# Schatten3.net
KiCad netlist of a schematic drawn in EAGLE
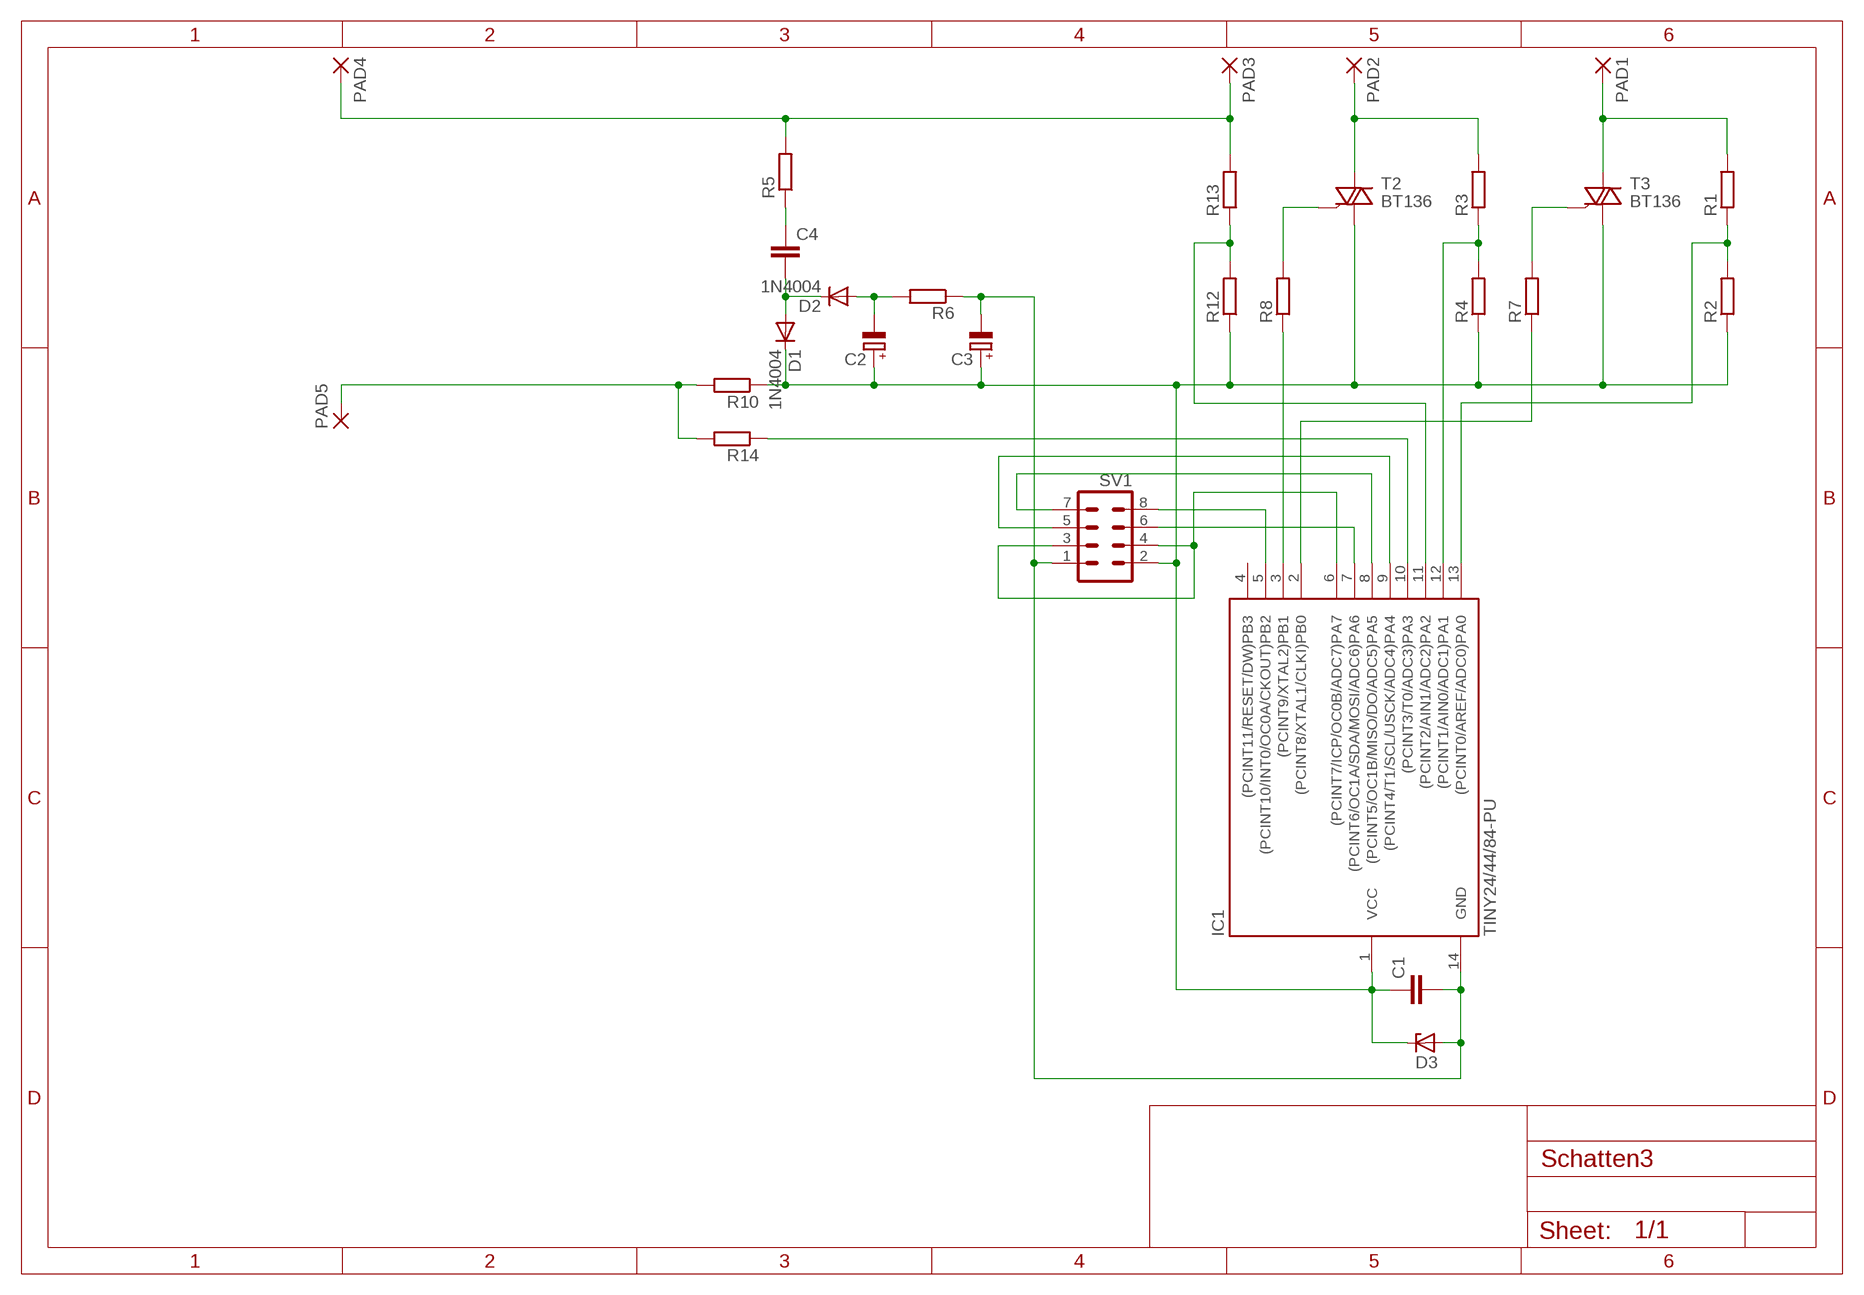
[diagram p0: schematic, sheet 1]

(export (version "E")
  (design (tool "Eeschema 10.0.6"))
  (components
    (comp (ref "C1")
      (value "C-EUC3225")
      (footprint "eagle-import:C3225")
      (libsource (lib "eagle-import") (part "C-EUC3225"))
    )
    (comp (ref "C2")
      (value "CPOL-EUE5-8.5")
      (footprint "eagle-import:E5-8,5")
      (libsource (lib "eagle-import") (part "CPOL-EUE5-8.5"))
    )
    (comp (ref "C3")
      (value "CPOL-EUE5-8.5")
      (footprint "eagle-import:E5-8,5")
      (libsource (lib "eagle-import") (part "CPOL-EUE5-8.5"))
    )
    (comp (ref "C4")
      (value "C-EU150-064X183")
      (footprint "eagle-import:C150-064X183")
      (libsource (lib "eagle-import") (part "C-EU150-064X183"))
    )
    (comp (ref "D1")
      (value "1N4004")
      (footprint "eagle-import:DO41-10")
      (libsource (lib "eagle-import") (part "1N4004"))
    )
    (comp (ref "D2")
      (value "1N4004")
      (footprint "eagle-import:DO41-10")
      (libsource (lib "eagle-import") (part "1N4004"))
    )
    (comp (ref "D3")
      (value "ZENER-DIODEZD-7.5")
      (footprint "eagle-import:ZDIO-7.5")
      (libsource (lib "eagle-import") (part "ZENER-DIODEZD-7.5"))
    )
    (comp (ref "IC1")
      (value "TINY24/44/84-PU")
      (footprint "eagle-import:DIL14")
      (libsource (lib "eagle-import") (part "TINY24/44/84-PU"))
    )
    (comp (ref "PAD1")
      (value "1,6/0,9")
      (footprint "eagle-import:1,6_0,9")
      (libsource (lib "eagle-import") (part "1,6/0,9"))
    )
    (comp (ref "PAD2")
      (value "1,6/0,9")
      (footprint "eagle-import:1,6_0,9")
      (libsource (lib "eagle-import") (part "1,6/0,9"))
    )
    (comp (ref "PAD3")
      (value "1,6/0,9")
      (footprint "eagle-import:1,6_0,9")
      (libsource (lib "eagle-import") (part "1,6/0,9"))
    )
    (comp (ref "PAD4")
      (value "1,6/0,9")
      (footprint "eagle-import:1,6_0,9")
      (libsource (lib "eagle-import") (part "1,6/0,9"))
    )
    (comp (ref "PAD5")
      (value "1,6/0,9")
      (footprint "eagle-import:1,6_0,9")
      (libsource (lib "eagle-import") (part "1,6/0,9"))
    )
    (comp (ref "R1")
      (value "R-EU_0207/10")
      (footprint "eagle-import:0207_10")
      (libsource (lib "eagle-import") (part "R-EU_0207/10"))
    )
    (comp (ref "R2")
      (value "R-EU_0207/10")
      (footprint "eagle-import:0207_10")
      (libsource (lib "eagle-import") (part "R-EU_0207/10"))
    )
    (comp (ref "R3")
      (value "R-EU_0207/10")
      (footprint "eagle-import:0207_10")
      (libsource (lib "eagle-import") (part "R-EU_0207/10"))
    )
    (comp (ref "R4")
      (value "R-EU_0207/10")
      (footprint "eagle-import:0207_10")
      (libsource (lib "eagle-import") (part "R-EU_0207/10"))
    )
    (comp (ref "R5")
      (value "R-EU_0207/10")
      (footprint "eagle-import:0207_10")
      (libsource (lib "eagle-import") (part "R-EU_0207/10"))
    )
    (comp (ref "R6")
      (value "R-EU_0207/10")
      (footprint "eagle-import:0207_10")
      (libsource (lib "eagle-import") (part "R-EU_0207/10"))
    )
    (comp (ref "R7")
      (value "R-EU_0207/10")
      (footprint "eagle-import:0207_10")
      (libsource (lib "eagle-import") (part "R-EU_0207/10"))
    )
    (comp (ref "R8")
      (value "R-EU_0207/10")
      (footprint "eagle-import:0207_10")
      (libsource (lib "eagle-import") (part "R-EU_0207/10"))
    )
    (comp (ref "R10")
      (value "R-EU_0207/10")
      (footprint "eagle-import:0207_10")
      (libsource (lib "eagle-import") (part "R-EU_0207/10"))
    )
    (comp (ref "R12")
      (value "R-EU_0207/10")
      (footprint "eagle-import:0207_10")
      (libsource (lib "eagle-import") (part "R-EU_0207/10"))
    )
    (comp (ref "R13")
      (value "R-EU_0207/10")
      (footprint "eagle-import:0207_10")
      (libsource (lib "eagle-import") (part "R-EU_0207/10"))
    )
    (comp (ref "R14")
      (value "R-EU_0207/10")
      (footprint "eagle-import:0207_10")
      (libsource (lib "eagle-import") (part "R-EU_0207/10"))
    )
    (comp (ref "SV1")
      (value "MA04-2")
      (footprint "eagle-import:MA04-2")
      (libsource (lib "eagle-import") (part "MA04-2"))
    )
    (comp (ref "T2")
      (value "BT136")
      (footprint "eagle-import:TO220AB")
      (libsource (lib "eagle-import") (part "BT136"))
    )
    (comp (ref "T3")
      (value "BT136")
      (footprint "eagle-import:TO220AB")
      (libsource (lib "eagle-import") (part "BT136"))
    )
  )
  (nets
    (net (code "1") (name "Net-(C2-Pad-)") (class "Default")
      (node (ref "C2") (pin "-") (pinfunction "-_-") (pintype "passive"))
      (node (ref "D2") (pin "A") (pinfunction "A_A") (pintype "passive"))
      (node (ref "R6") (pin "2") (pinfunction "2_2") (pintype "passive"))
    )
    (net (code "2") (name "Net-(C4-Pad1)") (class "Default")
      (node (ref "C4") (pin "1") (pinfunction "1_1") (pintype "passive"))
      (node (ref "R5") (pin "1") (pinfunction "1_1") (pintype "passive"))
    )
    (net (code "3") (name "Net-(C4-Pad2)") (class "Default")
      (node (ref "C4") (pin "2") (pinfunction "2_2") (pintype "passive"))
      (node (ref "D1") (pin "A") (pinfunction "A_A") (pintype "passive"))
      (node (ref "D2") (pin "C") (pinfunction "C_C") (pintype "passive"))
    )
    (net (code "4") (name "Net-(IC1-(PCINT0{slash}AREF{slash}ADC0)PA0)") (class "Default")
      (node (ref "IC1") (pin "13") (pinfunction "(PCINT0/AREF/ADC0)PA0_13") (pintype "bidirectional"))
      (node (ref "R1") (pin "1") (pinfunction "1_1") (pintype "passive"))
      (node (ref "R2") (pin "2") (pinfunction "2_2") (pintype "passive"))
    )
    (net (code "5") (name "Net-(IC1-(PCINT1{slash}AIN0{slash}ADC1)PA1)") (class "Default")
      (node (ref "IC1") (pin "12") (pinfunction "(PCINT1/AIN0/ADC1)PA1_12") (pintype "bidirectional"))
      (node (ref "R3") (pin "1") (pinfunction "1_1") (pintype "passive"))
      (node (ref "R4") (pin "2") (pinfunction "2_2") (pintype "passive"))
    )
    (net (code "6") (name "Net-(IC1-(PCINT2{slash}AIN1{slash}ADC2)PA2)") (class "Default")
      (node (ref "IC1") (pin "11") (pinfunction "(PCINT2/AIN1/ADC2)PA2_11") (pintype "bidirectional"))
      (node (ref "R12") (pin "2") (pinfunction "2_2") (pintype "passive"))
      (node (ref "R13") (pin "1") (pinfunction "1_1") (pintype "passive"))
    )
    (net (code "7") (name "Net-(IC1-(PCINT3{slash}T0{slash}ADC3)PA3)") (class "Default")
      (node (ref "IC1") (pin "10") (pinfunction "(PCINT3/T0/ADC3)PA3_10") (pintype "bidirectional"))
      (node (ref "R14") (pin "1") (pinfunction "1_1") (pintype "passive"))
    )
    (net (code "8") (name "Net-(IC1-(PCINT4{slash}T1{slash}SCL{slash}USCK{slash}ADC4)PA4)") (class "Default")
      (node (ref "IC1") (pin "9") (pinfunction "(PCINT4/T1/SCL/USCK/ADC4)PA4_9") (pintype "bidirectional"))
      (node (ref "SV1") (pin "5") (pinfunction "5_5") (pintype "passive"))
    )
    (net (code "9") (name "Net-(IC1-(PCINT5{slash}OC1B{slash}MISO{slash}DO{slash}ADC5)PA5)") (class "Default")
      (node (ref "IC1") (pin "8") (pinfunction "(PCINT5/OC1B/MISO/DO/ADC5)PA5_8") (pintype "bidirectional"))
      (node (ref "SV1") (pin "7") (pinfunction "7_7") (pintype "passive"))
    )
    (net (code "10") (name "Net-(IC1-(PCINT6{slash}OC1A{slash}SDA{slash}MOSI{slash}ADC6)PA6)") (class "Default")
      (node (ref "IC1") (pin "7") (pinfunction "(PCINT6/OC1A/SDA/MOSI/ADC6)PA6_7") (pintype "bidirectional"))
      (node (ref "SV1") (pin "6") (pinfunction "6_6") (pintype "passive"))
    )
    (net (code "11") (name "Net-(IC1-(PCINT7{slash}ICP{slash}OC0B{slash}ADC7)PA7)") (class "Default")
      (node (ref "IC1") (pin "6") (pinfunction "(PCINT7/ICP/OC0B/ADC7)PA7_6") (pintype "bidirectional"))
      (node (ref "SV1") (pin "3") (pinfunction "3_3") (pintype "passive"))
      (node (ref "SV1") (pin "4") (pinfunction "4_4") (pintype "passive"))
    )
    (net (code "12") (name "Net-(IC1-(PCINT8{slash}XTAL1{slash}CLKI)PB0)") (class "Default")
      (node (ref "IC1") (pin "2") (pinfunction "(PCINT8/XTAL1/CLKI)PB0_2") (pintype "bidirectional"))
      (node (ref "R7") (pin "1") (pinfunction "1_1") (pintype "passive"))
    )
    (net (code "13") (name "Net-(IC1-(PCINT9{slash}XTAL2)PB1)") (class "Default")
      (node (ref "IC1") (pin "3") (pinfunction "(PCINT9/XTAL2)PB1_3") (pintype "bidirectional"))
      (node (ref "R8") (pin "1") (pinfunction "1_1") (pintype "passive"))
    )
    (net (code "14") (name "Net-(IC1-(PCINT10{slash}INT0{slash}OC0A{slash}CKOUT)PB2)") (class "Default")
      (node (ref "IC1") (pin "5") (pinfunction "(PCINT10/INT0/OC0A/CKOUT)PB2_5") (pintype "bidirectional"))
      (node (ref "SV1") (pin "8") (pinfunction "8_8") (pintype "passive"))
    )
    (net (code "15") (name "Net-(IC1-GND)") (class "Default")
      (node (ref "C1") (pin "2") (pinfunction "2_2") (pintype "passive"))
      (node (ref "C3") (pin "-") (pinfunction "-_-") (pintype "passive"))
      (node (ref "D3") (pin "A") (pinfunction "A_A") (pintype "passive"))
      (node (ref "IC1") (pin "14") (pinfunction "GND_14") (pintype "power_in"))
      (node (ref "R6") (pin "1") (pinfunction "1_1") (pintype "passive"))
      (node (ref "SV1") (pin "1") (pinfunction "1_1") (pintype "passive"))
    )
    (net (code "16") (name "Net-(IC1-VCC)") (class "Default")
      (node (ref "C1") (pin "1") (pinfunction "1_1") (pintype "passive"))
      (node (ref "C2") (pin "+") (pinfunction "+_+") (pintype "passive"))
      (node (ref "C3") (pin "+") (pinfunction "+_+") (pintype "passive"))
      (node (ref "D1") (pin "C") (pinfunction "C_C") (pintype "passive"))
      (node (ref "D3") (pin "C") (pinfunction "C_C") (pintype "passive"))
      (node (ref "IC1") (pin "1") (pinfunction "VCC_1") (pintype "power_in"))
      (node (ref "R10") (pin "1") (pinfunction "1_1") (pintype "passive"))
      (node (ref "R12") (pin "1") (pinfunction "1_1") (pintype "passive"))
      (node (ref "R2") (pin "1") (pinfunction "1_1") (pintype "passive"))
      (node (ref "R4") (pin "1") (pinfunction "1_1") (pintype "passive"))
      (node (ref "SV1") (pin "2") (pinfunction "2_2") (pintype "passive"))
      (node (ref "T2") (pin "1") (pinfunction "A1_1") (pintype "passive"))
      (node (ref "T3") (pin "1") (pinfunction "A1_1") (pintype "passive"))
    )
    (net (code "17") (name "Net-(PAD1-P)") (class "Default")
      (node (ref "PAD1") (pin "1") (pinfunction "P_1") (pintype "passive"))
      (node (ref "R1") (pin "2") (pinfunction "2_2") (pintype "passive"))
      (node (ref "T3") (pin "2") (pinfunction "A2_2") (pintype "passive"))
    )
    (net (code "18") (name "Net-(PAD2-P)") (class "Default")
      (node (ref "PAD2") (pin "1") (pinfunction "P_1") (pintype "passive"))
      (node (ref "R3") (pin "2") (pinfunction "2_2") (pintype "passive"))
      (node (ref "T2") (pin "2") (pinfunction "A2_2") (pintype "passive"))
    )
    (net (code "19") (name "Net-(PAD3-P)") (class "Default")
      (node (ref "PAD3") (pin "1") (pinfunction "P_1") (pintype "passive"))
      (node (ref "PAD4") (pin "1") (pinfunction "P_1") (pintype "passive"))
      (node (ref "R13") (pin "2") (pinfunction "2_2") (pintype "passive"))
      (node (ref "R5") (pin "2") (pinfunction "2_2") (pintype "passive"))
    )
    (net (code "20") (name "Net-(PAD5-P)") (class "Default")
      (node (ref "PAD5") (pin "1") (pinfunction "P_1") (pintype "passive"))
      (node (ref "R10") (pin "2") (pinfunction "2_2") (pintype "passive"))
      (node (ref "R14") (pin "2") (pinfunction "2_2") (pintype "passive"))
    )
    (net (code "21") (name "Net-(T2-G)") (class "Default")
      (node (ref "R8") (pin "2") (pinfunction "2_2") (pintype "passive"))
      (node (ref "T2") (pin "3") (pinfunction "G_3") (pintype "passive"))
    )
    (net (code "22") (name "Net-(T3-G)") (class "Default")
      (node (ref "R7") (pin "2") (pinfunction "2_2") (pintype "passive"))
      (node (ref "T3") (pin "3") (pinfunction "G_3") (pintype "passive"))
    )
    (net (code "23") (name "unconnected-(IC1-(PCINT11{slash}RESET{slash}DW)PB3-Pad4)") (class "Default")
      (node (ref "IC1") (pin "4") (pinfunction "(PCINT11/RESET/DW)PB3_4") (pintype "bidirectional"))
    )
  )
)
